# ET-FLASHEEPROM.net
KiCad netlist of a schematic drawn in Altium Designer
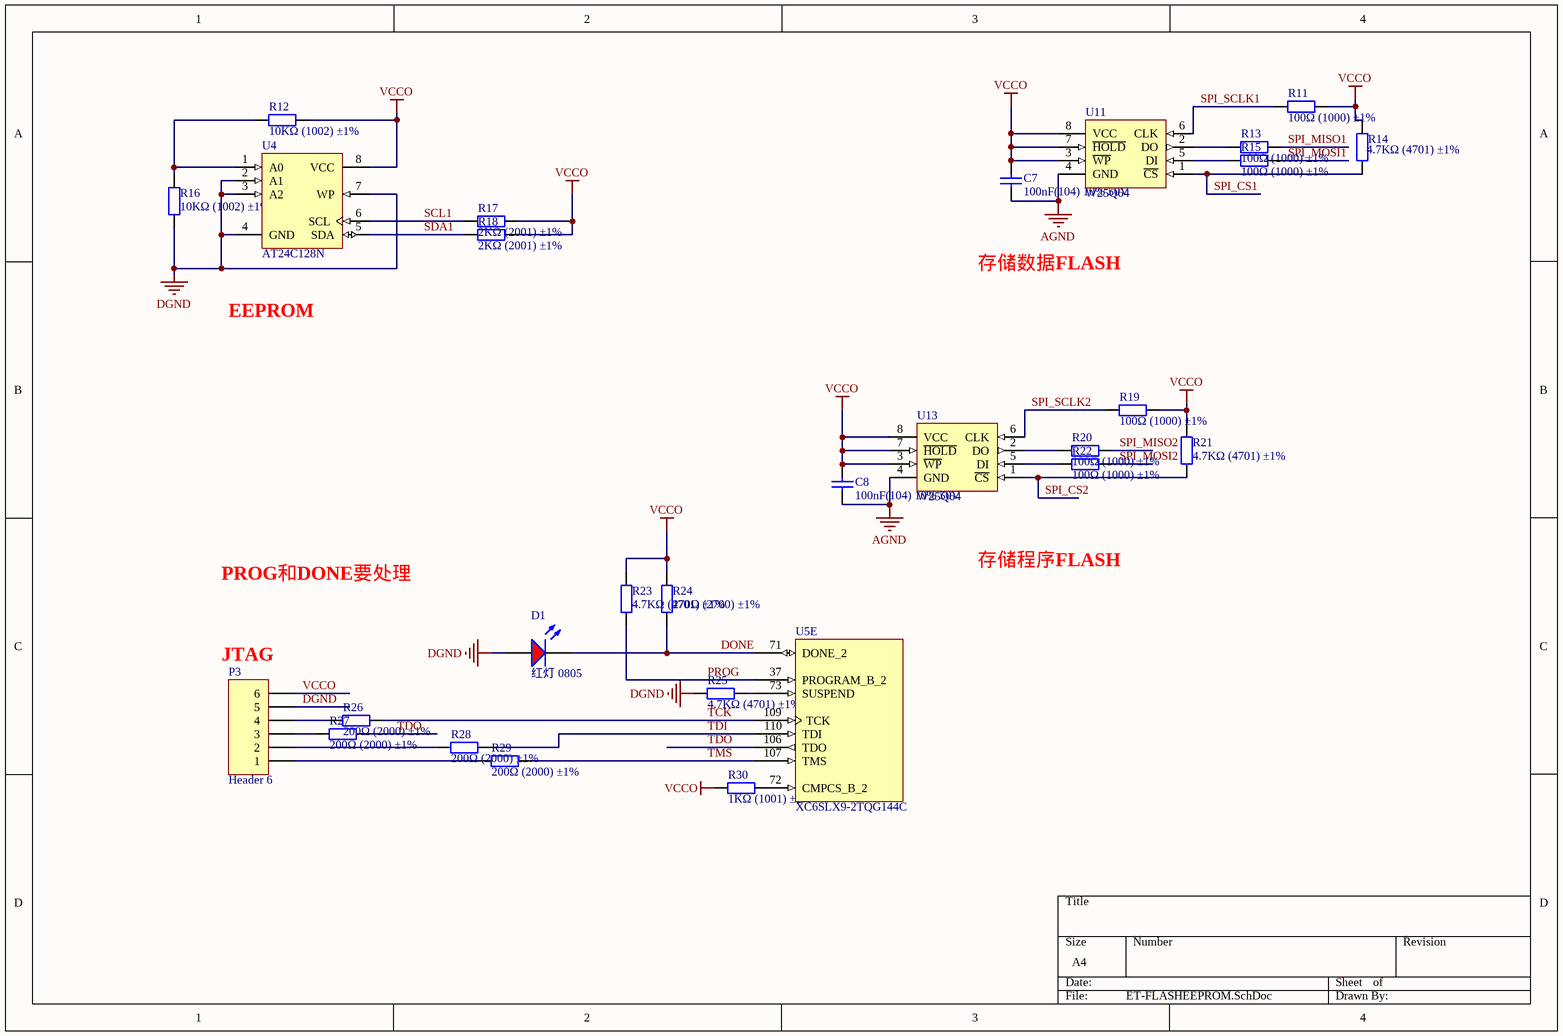
[diagram p0: ET-FLASHEEPROM.SchDoc]

(export (version "E")
  (design (tool "Eeschema 10.0.6"))
  (components
    (comp (ref "C7")
      (value "100nF(104) 10% 50V")
      (footprint "LC-0805_C")
      (description "贴片电容")
      (libsource (lib "Miscellaneous Devices LC") (part "0805 100nF(104) 10% 50V"))
    )
    (comp (ref "C8")
      (value "100nF(104) 10% 50V")
      (footprint "LC-0805_C")
      (description "贴片电容")
      (libsource (lib "Miscellaneous Devices LC") (part "0805 100nF(104) 10% 50V"))
    )
    (comp (ref "D1")
      (value "红灯 0805")
      (footprint "LC-0805_LED_S1")
      (description "发光二极管")
      (libsource (lib "Miscellaneous Devices LC") (part "0805 红灯"))
    )
    (comp (ref "P3")
      (value "Header 6")
      (footprint "HDR1X6")
      (description "Header, 6-Pin")
      (fields (field (name "PUBLISHER") "Altium Limited"))
      (libsource (lib "Miscellaneous Connectors") (part "Header 6"))
    )
    (comp (ref "R11")
      (value "100Ω (1000) ±1%")
      (footprint "LC-0805_R")
      (description "贴片电阻")
      (libsource (lib "Miscellaneous Devices LC") (part "0805 100Ω (1000) 1%"))
    )
    (comp (ref "R12")
      (value "10KΩ (1002) ±1%")
      (footprint "LC-0805_R")
      (description "贴片电阻")
      (libsource (lib "") (part "0805 10KΩ (1002) 1%_1"))
    )
    (comp (ref "R13")
      (value "100Ω (1000) ±1%")
      (footprint "LC-0805_R")
      (description "贴片电阻")
      (libsource (lib "Miscellaneous Devices LC") (part "0805 100Ω (1000) 1%"))
    )
    (comp (ref "R14")
      (value "4.7KΩ (4701) ±1%")
      (footprint "LC-0805_R")
      (description "贴片电阻")
      (libsource (lib "") (part "0805 4.7KΩ (4701) 1%_1"))
    )
    (comp (ref "R15")
      (value "100Ω (1000) ±1%")
      (footprint "LC-0805_R")
      (description "贴片电阻")
      (libsource (lib "Miscellaneous Devices LC") (part "0805 100Ω (1000) 1%"))
    )
    (comp (ref "R16")
      (value "10KΩ (1002) ±1%")
      (footprint "LC-0805_R")
      (description "贴片电阻")
      (libsource (lib "Miscellaneous Devices LC") (part "0805 10KΩ (1002) 1%"))
    )
    (comp (ref "R17")
      (value "2KΩ (2001) ±1%")
      (footprint "LC-0805_R")
      (description "贴片电阻")
      (libsource (lib "Miscellaneous Devices LC") (part "0805 2KΩ (2001) 1%"))
    )
    (comp (ref "R18")
      (value "2KΩ (2001) ±1%")
      (footprint "LC-0805_R")
      (description "贴片电阻")
      (libsource (lib "Miscellaneous Devices LC") (part "0805 2KΩ (2001) 1%"))
    )
    (comp (ref "R19")
      (value "100Ω (1000) ±1%")
      (footprint "LC-0805_R")
      (description "贴片电阻")
      (libsource (lib "Miscellaneous Devices LC") (part "0805 100Ω (1000) 1%"))
    )
    (comp (ref "R20")
      (value "100Ω (1000) ±1%")
      (footprint "LC-0805_R")
      (description "贴片电阻")
      (libsource (lib "Miscellaneous Devices LC") (part "0805 100Ω (1000) 1%"))
    )
    (comp (ref "R21")
      (value "4.7KΩ (4701) ±1%")
      (footprint "LC-0805_R")
      (description "贴片电阻")
      (libsource (lib "") (part "0805 4.7KΩ (4701) 1%_1"))
    )
    (comp (ref "R22")
      (value "100Ω (1000) ±1%")
      (footprint "LC-0805_R")
      (description "贴片电阻")
      (libsource (lib "Miscellaneous Devices LC") (part "0805 100Ω (1000) 1%"))
    )
    (comp (ref "R23")
      (value "4.7KΩ (4701) ±1%")
      (footprint "LC-0805_R")
      (description "贴片电阻")
      (libsource (lib "") (part "0805 4.7KΩ (4701) 1%_1"))
    )
    (comp (ref "R24")
      (value "270Ω (2700) ±1%")
      (footprint "LC-0805_R")
      (description "贴片电阻")
      (libsource (lib "Miscellaneous Devices LC") (part "0805 270Ω (2700) 1%"))
    )
    (comp (ref "R25")
      (value "4.7KΩ (4701) ±1%")
      (footprint "LC-0805_R")
      (description "贴片电阻")
      (libsource (lib "Miscellaneous Devices LC") (part "0805 4.7KΩ (4701) 1%"))
    )
    (comp (ref "R26")
      (value "200Ω (2000) ±1%")
      (footprint "LC-0805_R")
      (description "贴片电阻")
      (libsource (lib "Miscellaneous Devices LC") (part "0805 200Ω (2000) 1%"))
    )
    (comp (ref "R27")
      (value "200Ω (2000) ±1%")
      (footprint "LC-0805_R")
      (description "贴片电阻")
      (libsource (lib "Miscellaneous Devices LC") (part "0805 200Ω (2000) 1%"))
    )
    (comp (ref "R28")
      (value "200Ω (2000) ±1%")
      (footprint "LC-0805_R")
      (description "贴片电阻")
      (libsource (lib "Miscellaneous Devices LC") (part "0805 200Ω (2000) 1%"))
    )
    (comp (ref "R29")
      (value "200Ω (2000) ±1%")
      (footprint "LC-0805_R")
      (description "贴片电阻")
      (libsource (lib "Miscellaneous Devices LC") (part "0805 200Ω (2000) 1%"))
    )
    (comp (ref "R30")
      (value "1KΩ (1001) ±1%")
      (footprint "LC-0805_R")
      (description "贴片电阻")
      (libsource (lib "Miscellaneous Devices LC") (part "0805 1KΩ (1001) 1%"))
    )
    (comp (ref "U4")
      (value "AT24C128N")
      (footprint "8P3")
      (description "1Kbit (128 x 8), 2-wire Bus Automotive Serial EEPROM with Write Protect, 2.5V, 8-Pin TSSOP, Bulk")
      (fields (field (name "PUBLISHER") "Altium Limited"))
      (libsource (lib "Atmel Memory Serial EEPROM") (part "AT24C128N"))
    )
    (comp (ref "U5")
      (value "XC6SLX9-2TQG144C")
      (footprint "TQG144_N")
      (fields (field (name "PUBLISHER") "Altium Limited"))
      (libsource (lib "Xilinx Spartan-6") (part "XC6SLX9-2TQG144C"))
    )
    (comp (ref "U11")
      (value "W25Q64")
      (footprint "LC-SOIC-8_208mil")
      (libsource (lib "My Library") (part "W25Q64"))
    )
    (comp (ref "U13")
      (value "W25Q64")
      (footprint "LC-SOIC-8_208mil")
      (libsource (lib "My Library") (part "W25Q64"))
    )
  )
  (nets
    (net (code "1") (name "/DONE") (class "Default")
      (node (ref "D1") (pin "K") (pinfunction "K_K") (pintype "passive"))
      (node (ref "R24") (pin "1") (pinfunction "1_1") (pintype "passive"))
      (node (ref "U5") (pin "71") (pinfunction "DONE_2_71") (pintype "bidirectional"))
    )
    (net (code "2") (name "/PROG") (class "Default")
      (node (ref "R23") (pin "1") (pinfunction "1_1") (pintype "passive"))
      (node (ref "U5") (pin "37") (pinfunction "PROGRAM_B_2_37") (pintype "input"))
    )
    (net (code "3") (name "/SCL1") (class "Default")
      (node (ref "R17") (pin "1") (pinfunction "1_1") (pintype "passive"))
      (node (ref "U4") (pin "6") (pinfunction "SCL_6") (pintype "input"))
    )
    (net (code "4") (name "/SDA1") (class "Default")
      (node (ref "R18") (pin "1") (pinfunction "1_1") (pintype "passive"))
      (node (ref "U4") (pin "5") (pinfunction "SDA_5") (pintype "bidirectional"))
    )
    (net (code "5") (name "/SPI_CS1") (class "Default")
      (node (ref "R14") (pin "1") (pinfunction "1_1") (pintype "passive"))
      (node (ref "U11") (pin "1") (pinfunction "~{CS}_1") (pintype "input"))
    )
    (net (code "6") (name "/SPI_CS2") (class "Default")
      (node (ref "R21") (pin "1") (pinfunction "1_1") (pintype "passive"))
      (node (ref "U13") (pin "1") (pinfunction "~{CS}_1") (pintype "input"))
    )
    (net (code "7") (name "/SPI_MISO1") (class "Default")
      (node (ref "R13") (pin "2") (pinfunction "2_2") (pintype "passive"))
    )
    (net (code "8") (name "/SPI_MISO2") (class "Default")
      (node (ref "R20") (pin "2") (pinfunction "2_2") (pintype "passive"))
    )
    (net (code "9") (name "/SPI_MOSI1") (class "Default")
      (node (ref "R15") (pin "2") (pinfunction "2_2") (pintype "passive"))
    )
    (net (code "10") (name "/SPI_MOSI2") (class "Default")
      (node (ref "R22") (pin "2") (pinfunction "2_2") (pintype "passive"))
    )
    (net (code "11") (name "/SPI_SCLK1") (class "Default")
      (node (ref "R11") (pin "1") (pinfunction "1_1") (pintype "passive"))
      (node (ref "U11") (pin "6") (pinfunction "CLK_6") (pintype "input"))
    )
    (net (code "12") (name "/SPI_SCLK2") (class "Default")
      (node (ref "R19") (pin "1") (pinfunction "1_1") (pintype "passive"))
      (node (ref "U13") (pin "6") (pinfunction "CLK_6") (pintype "input"))
    )
    (net (code "13") (name "/TCK") (class "Default")
      (node (ref "R26") (pin "2") (pinfunction "2_2") (pintype "passive"))
      (node (ref "U5") (pin "109") (pinfunction "TCK_109") (pintype "input"))
    )
    (net (code "14") (name "/TDI") (class "Default")
      (node (ref "R28") (pin "2") (pinfunction "2_2") (pintype "passive"))
      (node (ref "U5") (pin "110") (pinfunction "TDI_110") (pintype "input"))
    )
    (net (code "15") (name "/TDO") (class "Default")
      (node (ref "R27") (pin "2") (pinfunction "2_2") (pintype "passive"))
      (node (ref "U5") (pin "106") (pinfunction "TDO_106") (pintype "output"))
    )
    (net (code "16") (name "/TMS") (class "Default")
      (node (ref "R29") (pin "2") (pinfunction "2_2") (pintype "passive"))
      (node (ref "U5") (pin "107") (pinfunction "TMS_107") (pintype "input"))
    )
    (net (code "17") (name "AGND") (class "Default")
      (node (ref "C7") (pin "1") (pinfunction "1_1") (pintype "passive"))
      (node (ref "C8") (pin "1") (pinfunction "1_1") (pintype "passive"))
      (node (ref "U11") (pin "4") (pinfunction "GND_4") (pintype "power_in"))
      (node (ref "U13") (pin "4") (pinfunction "GND_4") (pintype "power_in"))
    )
    (net (code "18") (name "DGND") (class "Default")
      (node (ref "D1") (pin "A") (pinfunction "A_A") (pintype "passive"))
      (node (ref "P3") (pin "5") (pinfunction "5_5") (pintype "passive"))
      (node (ref "R16") (pin "1") (pinfunction "1_1") (pintype "passive"))
      (node (ref "R25") (pin "1") (pinfunction "1_1") (pintype "passive"))
      (node (ref "U4") (pin "2") (pinfunction "A1_2") (pintype "input"))
      (node (ref "U4") (pin "3") (pinfunction "A2_3") (pintype "input"))
      (node (ref "U4") (pin "4") (pinfunction "GND_4") (pintype "power_in"))
      (node (ref "U4") (pin "7") (pinfunction "WP_7") (pintype "input"))
    )
    (net (code "19") (name "Net-(P3-Pad1)") (class "Default")
      (node (ref "P3") (pin "1") (pinfunction "1_1") (pintype "passive"))
      (node (ref "R29") (pin "1") (pinfunction "1_1") (pintype "passive"))
    )
    (net (code "20") (name "Net-(P3-Pad2)") (class "Default")
      (node (ref "P3") (pin "2") (pinfunction "2_2") (pintype "passive"))
      (node (ref "R28") (pin "1") (pinfunction "1_1") (pintype "passive"))
    )
    (net (code "21") (name "Net-(P3-Pad3)") (class "Default")
      (node (ref "P3") (pin "3") (pinfunction "3_3") (pintype "passive"))
      (node (ref "R27") (pin "1") (pinfunction "1_1") (pintype "passive"))
    )
    (net (code "22") (name "Net-(P3-Pad4)") (class "Default")
      (node (ref "P3") (pin "4") (pinfunction "4_4") (pintype "passive"))
      (node (ref "R26") (pin "1") (pinfunction "1_1") (pintype "passive"))
    )
    (net (code "23") (name "Net-(U4-A0)") (class "Default")
      (node (ref "R12") (pin "1") (pinfunction "1_1") (pintype "passive"))
      (node (ref "R16") (pin "2") (pinfunction "2_2") (pintype "passive"))
      (node (ref "U4") (pin "1") (pinfunction "A0_1") (pintype "input"))
    )
    (net (code "24") (name "Net-(U5E-CMPCS_B_2)") (class "Default")
      (node (ref "R30") (pin "2") (pinfunction "2_2") (pintype "passive"))
      (node (ref "U5") (pin "72") (pinfunction "CMPCS_B_2_72") (pintype "input"))
    )
    (net (code "25") (name "Net-(U5E-SUSPEND)") (class "Default")
      (node (ref "R25") (pin "2") (pinfunction "2_2") (pintype "passive"))
      (node (ref "U5") (pin "73") (pinfunction "SUSPEND_73") (pintype "input"))
    )
    (net (code "26") (name "Net-(U11-DI)") (class "Default")
      (node (ref "R15") (pin "1") (pinfunction "1_1") (pintype "passive"))
      (node (ref "U11") (pin "5") (pinfunction "DI_5") (pintype "input"))
    )
    (net (code "27") (name "Net-(U11-DO)") (class "Default")
      (node (ref "R13") (pin "1") (pinfunction "1_1") (pintype "passive"))
      (node (ref "U11") (pin "2") (pinfunction "DO_2") (pintype "output"))
    )
    (net (code "28") (name "Net-(U13-DI)") (class "Default")
      (node (ref "R22") (pin "1") (pinfunction "1_1") (pintype "passive"))
      (node (ref "U13") (pin "5") (pinfunction "DI_5") (pintype "input"))
    )
    (net (code "29") (name "Net-(U13-DO)") (class "Default")
      (node (ref "R20") (pin "1") (pinfunction "1_1") (pintype "passive"))
      (node (ref "U13") (pin "2") (pinfunction "DO_2") (pintype "output"))
    )
    (net (code "30") (name "VCCO") (class "Default")
      (node (ref "C7") (pin "2") (pinfunction "2_2") (pintype "passive"))
      (node (ref "C8") (pin "2") (pinfunction "2_2") (pintype "passive"))
      (node (ref "P3") (pin "6") (pinfunction "6_6") (pintype "passive"))
      (node (ref "R11") (pin "2") (pinfunction "2_2") (pintype "passive"))
      (node (ref "R12") (pin "2") (pinfunction "2_2") (pintype "passive"))
      (node (ref "R14") (pin "2") (pinfunction "2_2") (pintype "passive"))
      (node (ref "R17") (pin "2") (pinfunction "2_2") (pintype "passive"))
      (node (ref "R18") (pin "2") (pinfunction "2_2") (pintype "passive"))
      (node (ref "R19") (pin "2") (pinfunction "2_2") (pintype "passive"))
      (node (ref "R21") (pin "2") (pinfunction "2_2") (pintype "passive"))
      (node (ref "R23") (pin "2") (pinfunction "2_2") (pintype "passive"))
      (node (ref "R24") (pin "2") (pinfunction "2_2") (pintype "passive"))
      (node (ref "R30") (pin "1") (pinfunction "1_1") (pintype "passive"))
      (node (ref "U11") (pin "3") (pinfunction "~{WP}_3") (pintype "input"))
      (node (ref "U11") (pin "7") (pinfunction "~{HOLD}_7") (pintype "input"))
      (node (ref "U11") (pin "8") (pinfunction "VCC_8") (pintype "power_in"))
      (node (ref "U13") (pin "3") (pinfunction "~{WP}_3") (pintype "input"))
      (node (ref "U13") (pin "7") (pinfunction "~{HOLD}_7") (pintype "input"))
      (node (ref "U13") (pin "8") (pinfunction "VCC_8") (pintype "power_in"))
      (node (ref "U4") (pin "8") (pinfunction "VCC_8") (pintype "power_in"))
    )
  )
)
